# MRDT0003A1.net
KiCad netlist of a schematic drawn in EAGLE
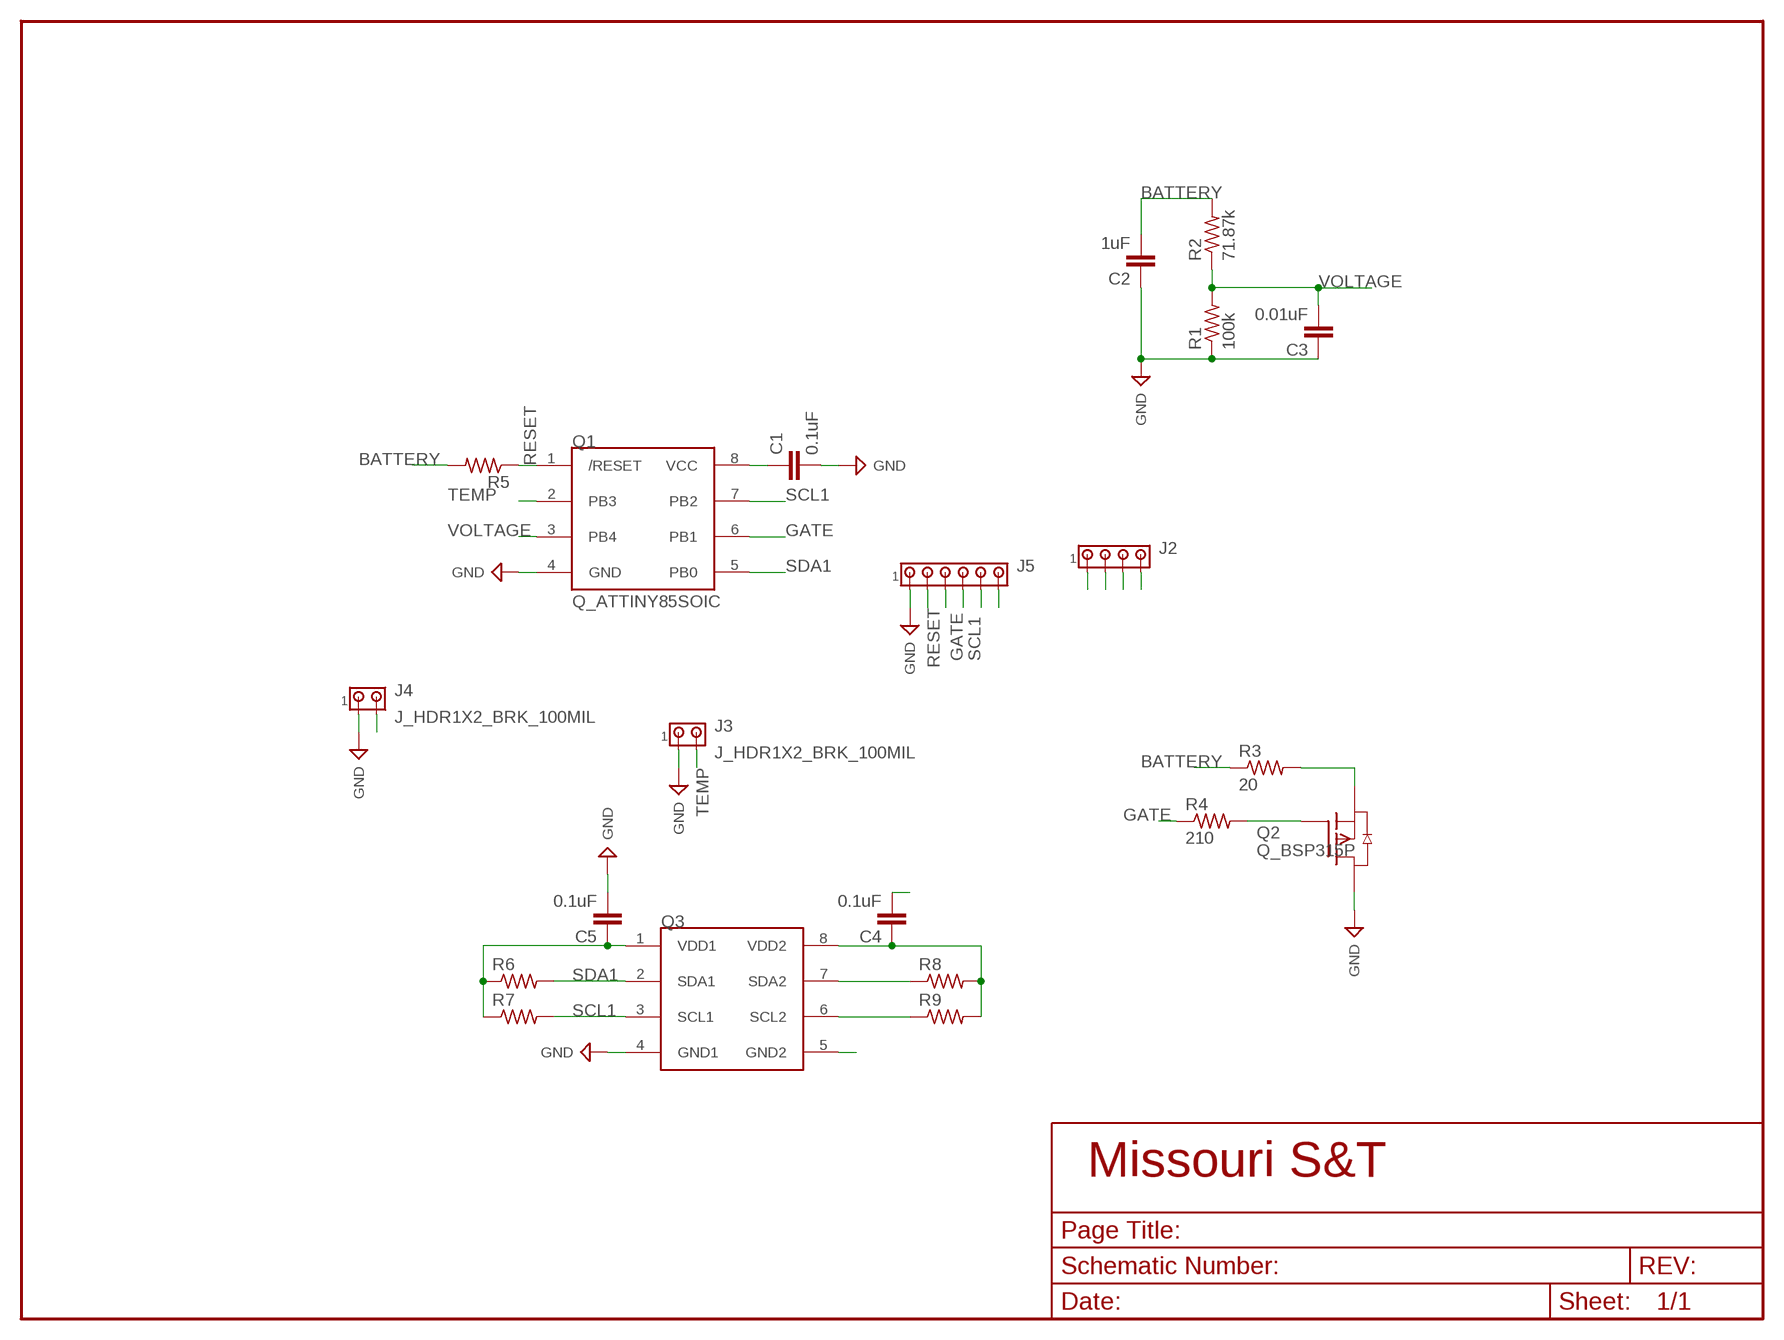
[diagram p0: schematic, sheet 1]

(export (version "E")
  (design (tool "Eeschema 10.0.6"))
  (components
    (comp (ref "C1")
      (value "0.1uF")
      (footprint "eagle-import:C_0805")
      (libsource (lib "eagle-import") (part "C_CAP_0805"))
    )
    (comp (ref "C2")
      (value "1uF")
      (footprint "eagle-import:C_0805")
      (libsource (lib "eagle-import") (part "C_CAP_0805"))
    )
    (comp (ref "C3")
      (value "0.01uF")
      (footprint "eagle-import:C_0805")
      (libsource (lib "eagle-import") (part "C_CAP_0805"))
    )
    (comp (ref "C4")
      (value "0.1uF")
      (footprint "eagle-import:C_0805")
      (libsource (lib "eagle-import") (part "C_CAP_0805"))
    )
    (comp (ref "C5")
      (value "0.1uF")
      (footprint "eagle-import:C_0805")
      (libsource (lib "eagle-import") (part "C_CAP_0805"))
    )
    (comp (ref "J2")
      (value "J_HDR1X4_BRK_100MIL")
      (footprint "eagle-import:J_BRK1X4_100MIL")
      (libsource (lib "eagle-import") (part "J_HDR1X4_BRK_100MIL"))
    )
    (comp (ref "J3")
      (value "J_HDR1X2_BRK_100MIL")
      (footprint "eagle-import:J_BRK1X2_100MIL")
      (libsource (lib "eagle-import") (part "J_HDR1X2_BRK_100MIL"))
    )
    (comp (ref "J4")
      (value "J_HDR1X2_BRK_100MIL")
      (footprint "eagle-import:J_BRK1X2_100MIL")
      (libsource (lib "eagle-import") (part "J_HDR1X2_BRK_100MIL"))
    )
    (comp (ref "J5")
      (value "J_HDR1X6_BRK_100MIL")
      (footprint "eagle-import:J_BRK1X6_100MIL")
      (libsource (lib "eagle-import") (part "J_HDR1X6_BRK_100MIL"))
    )
    (comp (ref "Q1")
      (value "Q_ATTINY85SOIC")
      (footprint "eagle-import:SOIC8")
      (libsource (lib "eagle-import") (part "Q_ATTINY85SOIC"))
    )
    (comp (ref "Q2")
      (value "Q_BSP315P")
      (footprint "eagle-import:SOT-223")
      (libsource (lib "eagle-import") (part "Q_BSP315P"))
    )
    (comp (ref "Q3")
      (value "Q_ADUM1250SOIC")
      (footprint "eagle-import:SOIC8")
      (libsource (lib "eagle-import") (part "Q_ADUM1250SOIC"))
    )
    (comp (ref "R1")
      (value "100k")
      (footprint "eagle-import:R_0805")
      (libsource (lib "eagle-import") (part "R_RES_0805"))
    )
    (comp (ref "R2")
      (value "71.87k")
      (footprint "eagle-import:R_0805")
      (libsource (lib "eagle-import") (part "R_RES_0805"))
    )
    (comp (ref "R3")
      (value "20")
      (footprint "eagle-import:R_2010")
      (libsource (lib "eagle-import") (part "R_RES_2010"))
    )
    (comp (ref "R4")
      (value "210")
      (footprint "eagle-import:R_0805")
      (libsource (lib "eagle-import") (part "R_RES_0805"))
    )
    (comp (ref "R5")
      (value "R_RES_0805")
      (footprint "eagle-import:R_0805")
      (libsource (lib "eagle-import") (part "R_RES_0805"))
    )
    (comp (ref "R6")
      (value "R_RES_0805")
      (footprint "eagle-import:R_0805")
      (libsource (lib "eagle-import") (part "R_RES_0805"))
    )
    (comp (ref "R7")
      (value "R_RES_1206")
      (footprint "eagle-import:R_1206")
      (libsource (lib "eagle-import") (part "R_RES_1206"))
    )
    (comp (ref "R8")
      (value "R_RES_1206")
      (footprint "eagle-import:R_1206")
      (libsource (lib "eagle-import") (part "R_RES_1206"))
    )
    (comp (ref "R9")
      (value "R_RES_1206")
      (footprint "eagle-import:R_1206")
      (libsource (lib "eagle-import") (part "R_RES_1206"))
    )
  )
  (nets
    (net (code "1") (name "/BATTERY") (class "Default")
      (node (ref "C1") (pin "1") (pinfunction "1_1") (pintype "passive"))
      (node (ref "C2") (pin "2") (pinfunction "2_2") (pintype "passive"))
      (node (ref "C5") (pin "1") (pinfunction "1_1") (pintype "passive"))
      (node (ref "J4") (pin "2") (pinfunction "2_2") (pintype "passive"))
      (node (ref "J5") (pin "6") (pinfunction "6_6") (pintype "passive"))
      (node (ref "Q1") (pin "8") (pinfunction "VCC_8") (pintype "bidirectional"))
      (node (ref "Q3") (pin "1") (pinfunction "VDD1_1") (pintype "bidirectional"))
      (node (ref "R2") (pin "2") (pinfunction "2_2") (pintype "passive"))
      (node (ref "R3") (pin "1") (pinfunction "1_1") (pintype "passive"))
      (node (ref "R5") (pin "2") (pinfunction "2_2") (pintype "passive"))
      (node (ref "R6") (pin "1") (pinfunction "1_1") (pintype "passive"))
      (node (ref "R7") (pin "1") (pinfunction "1_1") (pintype "passive"))
    )
    (net (code "2") (name "/GATE") (class "Default")
      (node (ref "J5") (pin "3") (pinfunction "3_3") (pintype "passive"))
      (node (ref "Q1") (pin "6") (pinfunction "PB1_6") (pintype "bidirectional"))
      (node (ref "R4") (pin "1") (pinfunction "1_1") (pintype "passive"))
    )
    (net (code "3") (name "/GND1") (class "Default")
      (node (ref "C4") (pin "2") (pinfunction "2_2") (pintype "passive"))
      (node (ref "J2") (pin "1") (pinfunction "1_1") (pintype "passive"))
      (node (ref "Q3") (pin "5") (pinfunction "GND2_5") (pintype "bidirectional"))
    )
    (net (code "4") (name "/RESET") (class "Default")
      (node (ref "J5") (pin "2") (pinfunction "2_2") (pintype "passive"))
      (node (ref "Q1") (pin "1") (pinfunction "/RESET_1") (pintype "bidirectional"))
      (node (ref "R5") (pin "1") (pinfunction "1_1") (pintype "passive"))
    )
    (net (code "5") (name "/SCL1") (class "Default")
      (node (ref "J5") (pin "4") (pinfunction "4_4") (pintype "passive"))
      (node (ref "Q1") (pin "7") (pinfunction "PB2_7") (pintype "bidirectional"))
      (node (ref "Q3") (pin "3") (pinfunction "SCL1_3") (pintype "bidirectional"))
      (node (ref "R7") (pin "2") (pinfunction "2_2") (pintype "passive"))
    )
    (net (code "6") (name "/SCL2") (class "Default")
      (node (ref "J2") (pin "3") (pinfunction "3_3") (pintype "passive"))
      (node (ref "Q3") (pin "6") (pinfunction "SCL2_6") (pintype "bidirectional"))
      (node (ref "R9") (pin "1") (pinfunction "1_1") (pintype "passive"))
    )
    (net (code "7") (name "/SDA1") (class "Default")
      (node (ref "J5") (pin "5") (pinfunction "5_5") (pintype "passive"))
      (node (ref "Q1") (pin "5") (pinfunction "PB0_5") (pintype "bidirectional"))
      (node (ref "Q3") (pin "2") (pinfunction "SDA1_2") (pintype "bidirectional"))
      (node (ref "R6") (pin "2") (pinfunction "2_2") (pintype "passive"))
    )
    (net (code "8") (name "/SDA2") (class "Default")
      (node (ref "J2") (pin "2") (pinfunction "2_2") (pintype "passive"))
      (node (ref "Q3") (pin "7") (pinfunction "SDA2_7") (pintype "bidirectional"))
      (node (ref "R8") (pin "1") (pinfunction "1_1") (pintype "passive"))
    )
    (net (code "9") (name "/TEMP") (class "Default")
      (node (ref "J3") (pin "2") (pinfunction "2_2") (pintype "passive"))
      (node (ref "Q1") (pin "2") (pinfunction "PB3_2") (pintype "bidirectional"))
    )
    (net (code "10") (name "/VCC1") (class "Default")
      (node (ref "C4") (pin "1") (pinfunction "1_1") (pintype "passive"))
      (node (ref "J2") (pin "4") (pinfunction "4_4") (pintype "passive"))
      (node (ref "Q3") (pin "8") (pinfunction "VDD2_8") (pintype "bidirectional"))
      (node (ref "R8") (pin "2") (pinfunction "2_2") (pintype "passive"))
      (node (ref "R9") (pin "2") (pinfunction "2_2") (pintype "passive"))
    )
    (net (code "11") (name "/VOLTAGE") (class "Default")
      (node (ref "C3") (pin "2") (pinfunction "2_2") (pintype "passive"))
      (node (ref "Q1") (pin "3") (pinfunction "PB4_3") (pintype "bidirectional"))
      (node (ref "R1") (pin "2") (pinfunction "2_2") (pintype "passive"))
      (node (ref "R2") (pin "1") (pinfunction "1_1") (pintype "passive"))
    )
    (net (code "12") (name "Net-(Q2-G)") (class "Default")
      (node (ref "Q2") (pin "1") (pinfunction "G_1") (pintype "passive"))
      (node (ref "R4") (pin "2") (pinfunction "2_2") (pintype "passive"))
    )
    (net (code "13") (name "Net-(Q2-S)") (class "Default")
      (node (ref "Q2") (pin "3") (pinfunction "S_3") (pintype "passive"))
      (node (ref "R3") (pin "2") (pinfunction "2_2") (pintype "passive"))
    )
    (net (code "14") (name "SUP_GND") (class "Default")
      (node (ref "C1") (pin "2") (pinfunction "2_2") (pintype "passive"))
      (node (ref "C2") (pin "1") (pinfunction "1_1") (pintype "passive"))
      (node (ref "C3") (pin "1") (pinfunction "1_1") (pintype "passive"))
      (node (ref "C5") (pin "2") (pinfunction "2_2") (pintype "passive"))
      (node (ref "J3") (pin "1") (pinfunction "1_1") (pintype "passive"))
      (node (ref "J4") (pin "1") (pinfunction "1_1") (pintype "passive"))
      (node (ref "J5") (pin "1") (pinfunction "1_1") (pintype "passive"))
      (node (ref "Q1") (pin "4") (pinfunction "GND_4") (pintype "bidirectional"))
      (node (ref "Q2") (pin "2") (pinfunction "D_2") (pintype "passive"))
      (node (ref "Q3") (pin "4") (pinfunction "GND1_4") (pintype "bidirectional"))
      (node (ref "R1") (pin "1") (pinfunction "1_1") (pintype "passive"))
    )
  )
)
